# SolenoidWiring.net
KiCad netlist of a schematic drawn in EAGLE
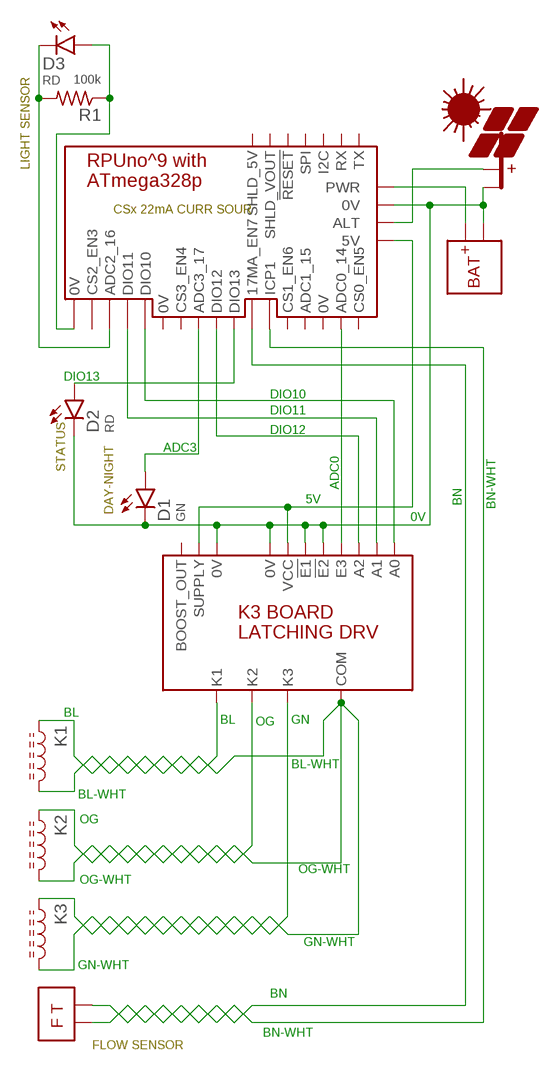
[diagram p0: schematic, sheet 1]

(export (version "E")
  (design (tool "Eeschema 10.0.6"))
  (components
    (comp (ref "BM1")
      (value "RPUNO")
      (footprint "eagle-import:NA-30")
      (libsource (lib "eagle-import") (part "RPUNO"))
    )
    (comp (ref "D1")
      (value "GN")
      (footprint "eagle-import:LED5MM")
      (libsource (lib "eagle-import") (part "LED5MM"))
    )
    (comp (ref "D2")
      (value "RD")
      (footprint "eagle-import:LED5MM")
      (libsource (lib "eagle-import") (part "LED5MM"))
    )
    (comp (ref "D3")
      (value "RD")
      (footprint "eagle-import:LED5MM")
      (libsource (lib "eagle-import") (part "LED5MM"))
    )
    (comp (ref "K1")
      (value "L0805")
      (footprint "eagle-import:C0805(2012)")
      (libsource (lib "eagle-import") (part "L0805"))
    )
    (comp (ref "K2")
      (value "L0805")
      (footprint "eagle-import:C0805(2012)")
      (libsource (lib "eagle-import") (part "L0805"))
    )
    (comp (ref "K3")
      (value "L0805")
      (footprint "eagle-import:C0805(2012)")
      (libsource (lib "eagle-import") (part "L0805"))
    )
    (comp (ref "PV4")
      (value "PV")
      (footprint "eagle-import:NA-30")
      (libsource (lib "eagle-import") (part "PV"))
    )
    (comp (ref "R1")
      (value "100k")
      (footprint "eagle-import:C0805(2012)")
      (libsource (lib "eagle-import") (part "R0805"))
    )
    (comp (ref "U$1")
      (value "K3")
      (footprint "eagle-import:NA-30")
      (libsource (lib "eagle-import") (part "K3"))
    )
    (comp (ref "U$2")
      (value "FT")
      (footprint "eagle-import:NA-30")
      (libsource (lib "eagle-import") (part "FT"))
    )
    (comp (ref "U$7")
      (value "BAT")
      (footprint "eagle-import:NA-30")
      (libsource (lib "eagle-import") (part "BAT"))
    )
  )
  (nets
    (net (code "1") (name "/0V") (class "Default")
      (node (ref "BM1") (pin "9") (pinfunction "0V_9") (pintype "bidirectional"))
      (node (ref "D1") (pin "K") (pinfunction "K_K") (pintype "passive"))
      (node (ref "D2") (pin "K") (pinfunction "K_K") (pintype "passive"))
      (node (ref "PV4") (pin "2") (pinfunction "-PV_2") (pintype "bidirectional"))
      (node (ref "U$1") (pin "1") (pinfunction "~{E1}_1") (pintype "bidirectional"))
      (node (ref "U$1") (pin "2") (pinfunction "~{E2}_2") (pintype "bidirectional"))
      (node (ref "U$1") (pin "3") (pinfunction "0V_3") (pintype "bidirectional"))
      (node (ref "U$1") (pin "4") (pinfunction "0V_4") (pintype "bidirectional"))
      (node (ref "U$7") (pin "2") (pinfunction "-BAT_2") (pintype "bidirectional"))
    )
    (net (code "2") (name "/5V") (class "Default")
      (node (ref "BM1") (pin "19") (pinfunction "5V_19") (pintype "bidirectional"))
      (node (ref "U$1") (pin "14") (pinfunction "SUPPLY_14") (pintype "bidirectional"))
      (node (ref "U$1") (pin "15") (pinfunction "VCC_15") (pintype "bidirectional"))
    )
    (net (code "3") (name "/ADC0") (class "Default")
      (node (ref "BM1") (pin "11") (pinfunction "ADC0_14_11") (pintype "bidirectional"))
      (node (ref "U$1") (pin "10") (pinfunction "E3_10") (pintype "bidirectional"))
    )
    (net (code "4") (name "/ADC3") (class "Default")
      (node (ref "BM1") (pin "16") (pinfunction "ADC3_17_16") (pintype "bidirectional"))
      (node (ref "D1") (pin "A") (pinfunction "A_A") (pintype "passive"))
    )
    (net (code "5") (name "/BL") (class "Default")
      (node (ref "K1") (pin "1") (pinfunction "1_1") (pintype "passive"))
      (node (ref "U$1") (pin "11") (pinfunction "K1_11") (pintype "bidirectional"))
    )
    (net (code "6") (name "/BL-WHT") (class "Default")
      (node (ref "K1") (pin "2") (pinfunction "2_2") (pintype "passive"))
      (node (ref "U$1") (pin "9") (pinfunction "COM_9") (pintype "bidirectional"))
    )
    (net (code "7") (name "/BN") (class "Default")
      (node (ref "BM1") (pin "21") (pinfunction "17MA_EN7_21") (pintype "bidirectional"))
      (node (ref "U$2") (pin "2") (pinfunction "PWR_2") (pintype "bidirectional"))
    )
    (net (code "8") (name "/BN-WHT") (class "Default")
      (node (ref "BM1") (pin "12") (pinfunction "ICP1_12") (pintype "bidirectional"))
      (node (ref "U$2") (pin "1") (pinfunction "PL_1") (pintype "bidirectional"))
    )
    (net (code "9") (name "/DIO10") (class "Default")
      (node (ref "BM1") (pin "15") (pinfunction "DIO10_15") (pintype "bidirectional"))
      (node (ref "U$1") (pin "5") (pinfunction "A0_5") (pintype "bidirectional"))
    )
    (net (code "10") (name "/DIO11") (class "Default")
      (node (ref "BM1") (pin "14") (pinfunction "DIO11_14") (pintype "bidirectional"))
      (node (ref "U$1") (pin "6") (pinfunction "A1_6") (pintype "bidirectional"))
    )
    (net (code "11") (name "/DIO12") (class "Default")
      (node (ref "BM1") (pin "17") (pinfunction "DIO12_17") (pintype "bidirectional"))
      (node (ref "U$1") (pin "7") (pinfunction "A2_7") (pintype "bidirectional"))
    )
    (net (code "12") (name "/DIO13") (class "Default")
      (node (ref "BM1") (pin "18") (pinfunction "DIO13_18") (pintype "bidirectional"))
      (node (ref "D2") (pin "A") (pinfunction "A_A") (pintype "passive"))
    )
    (net (code "13") (name "/GN") (class "Default")
      (node (ref "K3") (pin "1") (pinfunction "1_1") (pintype "passive"))
      (node (ref "U$1") (pin "13") (pinfunction "K3_13") (pintype "bidirectional"))
    )
    (net (code "14") (name "/GN-WHT") (class "Default")
      (node (ref "K3") (pin "2") (pinfunction "2_2") (pintype "passive"))
    )
    (net (code "15") (name "/OG") (class "Default")
      (node (ref "K2") (pin "1") (pinfunction "1_1") (pintype "passive"))
      (node (ref "U$1") (pin "12") (pinfunction "K2_12") (pintype "bidirectional"))
    )
    (net (code "16") (name "/OG-WHT") (class "Default")
      (node (ref "K2") (pin "2") (pinfunction "2_2") (pintype "passive"))
    )
    (net (code "17") (name "Net-(BM1-0V-Pad27)") (class "Default")
      (node (ref "BM1") (pin "27") (pinfunction "0V_27") (pintype "bidirectional"))
      (node (ref "D3") (pin "A") (pinfunction "A_A") (pintype "passive"))
      (node (ref "R1") (pin "1") (pinfunction "1_1") (pintype "passive"))
    )
    (net (code "18") (name "Net-(BM1-ADC2_16)") (class "Default")
      (node (ref "BM1") (pin "13") (pinfunction "ADC2_16_13") (pintype "bidirectional"))
      (node (ref "D3") (pin "K") (pinfunction "K_K") (pintype "passive"))
      (node (ref "R1") (pin "2") (pinfunction "2_2") (pintype "passive"))
    )
    (net (code "19") (name "Net-(BM1-ALT)") (class "Default")
      (node (ref "BM1") (pin "20") (pinfunction "ALT_20") (pintype "bidirectional"))
      (node (ref "PV4") (pin "1") (pinfunction "+PV_1") (pintype "bidirectional"))
    )
    (net (code "20") (name "Net-(BM1-PWR)") (class "Default")
      (node (ref "BM1") (pin "8") (pinfunction "PWR_8") (pintype "bidirectional"))
      (node (ref "U$7") (pin "1") (pinfunction "+BAT_1") (pintype "bidirectional"))
    )
    (net (code "21") (name "unconnected-(BM1-0V-Pad26)") (class "Default")
      (node (ref "BM1") (pin "26") (pinfunction "0V_26") (pintype "bidirectional"))
    )
    (net (code "22") (name "unconnected-(BM1-0V-Pad28)") (class "Default")
      (node (ref "BM1") (pin "28") (pinfunction "0V_28") (pintype "bidirectional"))
    )
    (net (code "23") (name "unconnected-(BM1-ADC1_15-Pad10)") (class "Default")
      (node (ref "BM1") (pin "10") (pinfunction "ADC1_15_10") (pintype "bidirectional"))
    )
    (net (code "24") (name "unconnected-(BM1-CS0_EN5-Pad23)") (class "Default")
      (node (ref "BM1") (pin "23") (pinfunction "CS0_EN5_23") (pintype "bidirectional"))
    )
    (net (code "25") (name "unconnected-(BM1-CS1_EN6-Pad22)") (class "Default")
      (node (ref "BM1") (pin "22") (pinfunction "CS1_EN6_22") (pintype "bidirectional"))
    )
    (net (code "26") (name "unconnected-(BM1-CS2_EN3-Pad24)") (class "Default")
      (node (ref "BM1") (pin "24") (pinfunction "CS2_EN3_24") (pintype "bidirectional"))
    )
    (net (code "27") (name "unconnected-(BM1-CS3_EN4-Pad29)") (class "Default")
      (node (ref "BM1") (pin "29") (pinfunction "CS3_EN4_29") (pintype "bidirectional"))
    )
    (net (code "28") (name "unconnected-(BM1-I2C-Pad3)") (class "Default")
      (node (ref "BM1") (pin "3") (pinfunction "I2C_3") (pintype "bidirectional"))
    )
    (net (code "29") (name "unconnected-(BM1-RX-Pad2)") (class "Default")
      (node (ref "BM1") (pin "2") (pinfunction "RX_2") (pintype "bidirectional"))
    )
    (net (code "30") (name "unconnected-(BM1-SHLD_5V-Pad6)") (class "Default")
      (node (ref "BM1") (pin "6") (pinfunction "SHLD_5V_6") (pintype "bidirectional"))
    )
    (net (code "31") (name "unconnected-(BM1-SHLD_VOUT-Pad7)") (class "Default")
      (node (ref "BM1") (pin "7") (pinfunction "SHLD_VOUT_7") (pintype "bidirectional"))
    )
    (net (code "32") (name "unconnected-(BM1-SPI-Pad4)") (class "Default")
      (node (ref "BM1") (pin "4") (pinfunction "SPI_4") (pintype "bidirectional"))
    )
    (net (code "33") (name "unconnected-(BM1-TX-Pad1)") (class "Default")
      (node (ref "BM1") (pin "1") (pinfunction "TX_1") (pintype "bidirectional"))
    )
    (net (code "34") (name "unconnected-(BM1-~{RESET}-Pad5)") (class "Default")
      (node (ref "BM1") (pin "5") (pinfunction "~{RESET}_5") (pintype "bidirectional"))
    )
    (net (code "35") (name "unconnected-(U$1-BOOST_OUT-Pad8)") (class "Default")
      (node (ref "U$1") (pin "8") (pinfunction "BOOST_OUT_8") (pintype "bidirectional"))
    )
  )
)
